# gloria.net
KiCad netlist of a schematic drawn in EAGLE
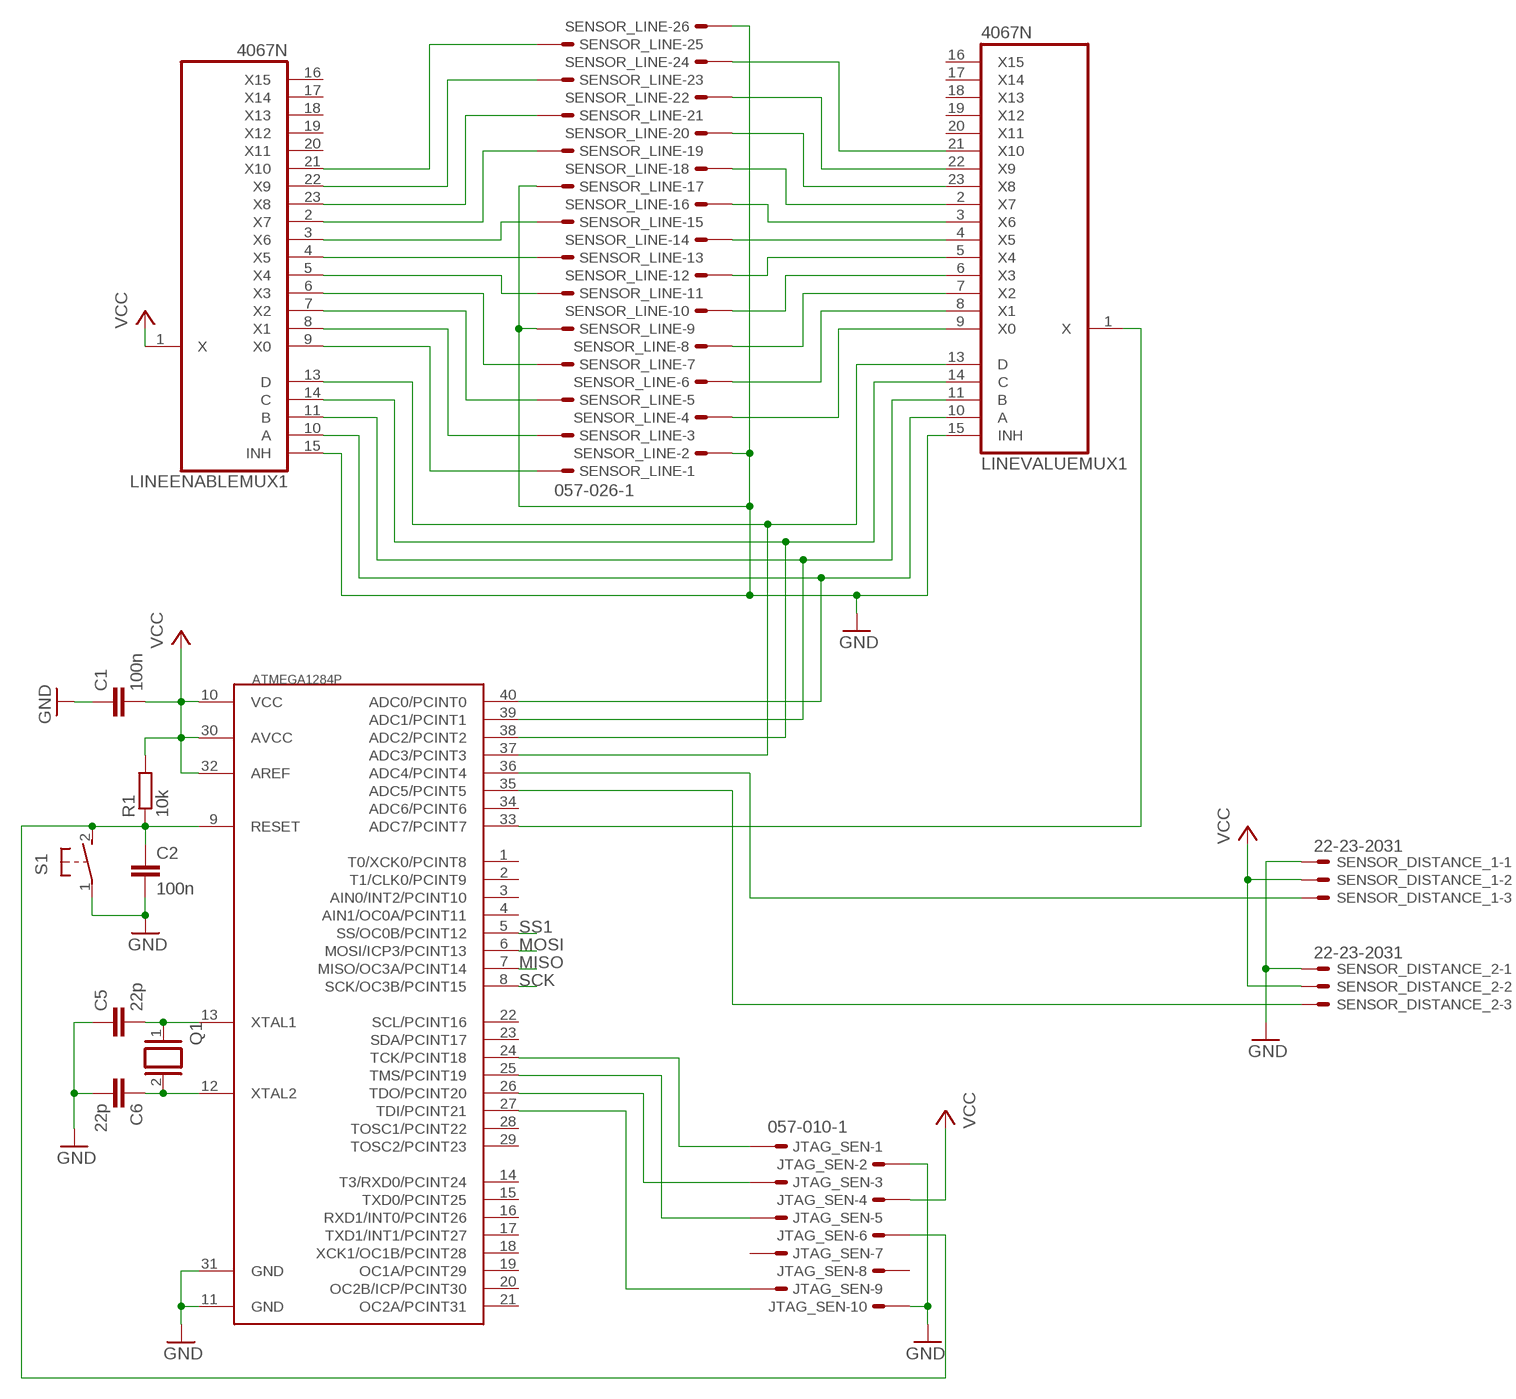
[diagram p0: schematic, sheet 1]
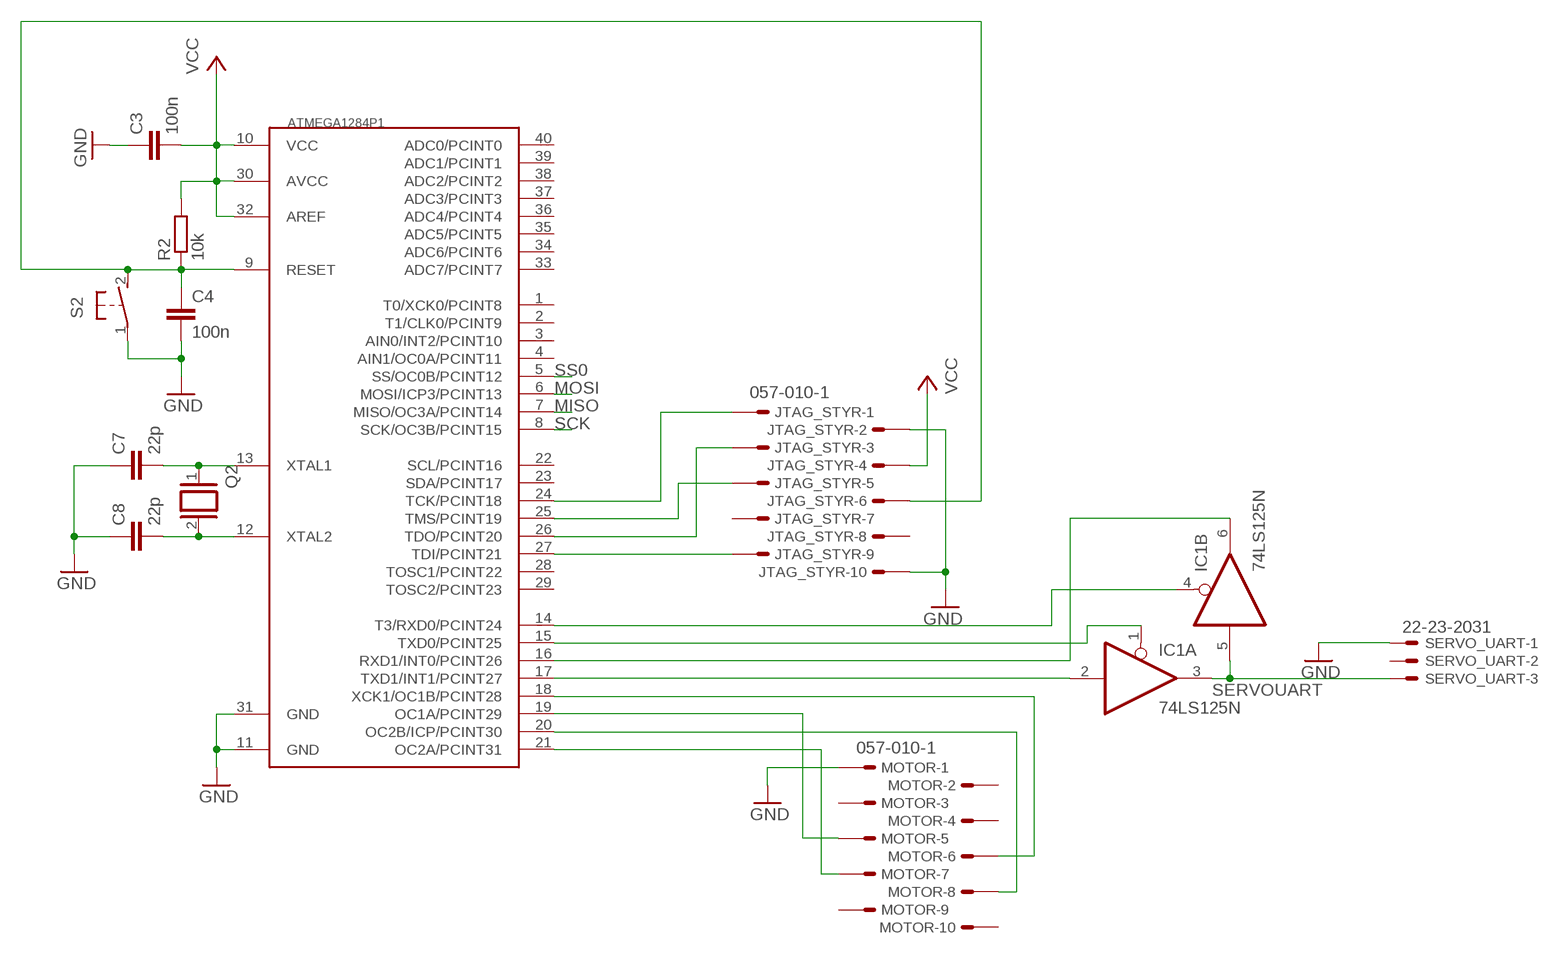
[diagram p1: schematic, sheet 2]
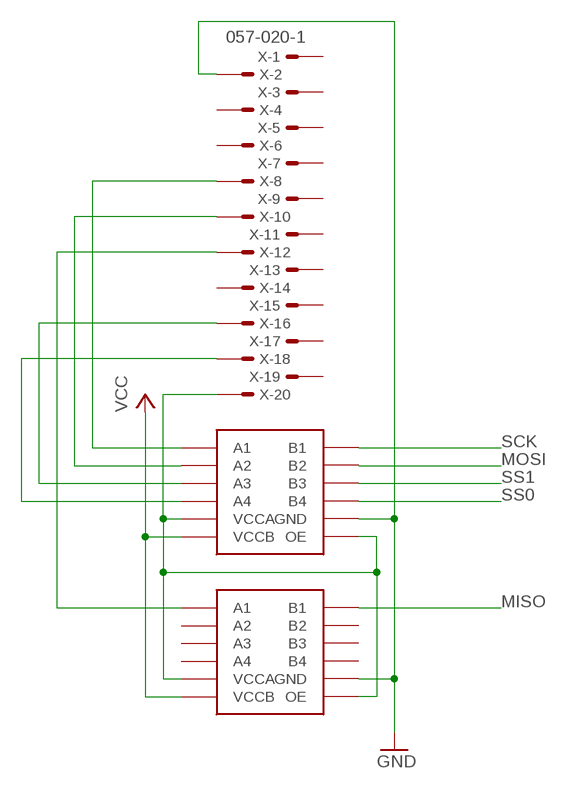
[diagram p2: schematic, sheet 3]

(export (version "E")
  (design (tool "Eeschema 10.0.6"))
  (components
    (comp (ref "ATMEGA1284P1")
      (value "MEGA1284P")
      (footprint "eagle-import:DIL40")
      (libsource (lib "eagle-import") (part "MEGA1284P"))
    )
    (comp (ref "C3")
      (value "100n")
      (footprint "eagle-import:C025-050X050")
      (libsource (lib "eagle-import") (part "C-EU025-050X050"))
    )
    (comp (ref "C4")
      (value "100n")
      (footprint "eagle-import:C025-050X050")
      (libsource (lib "eagle-import") (part "C-EU025-050X050"))
    )
    (comp (ref "C7")
      (value "22p")
      (footprint "eagle-import:C025-050X050")
      (libsource (lib "eagle-import") (part "C-EU025-050X050"))
    )
    (comp (ref "C8")
      (value "22p")
      (footprint "eagle-import:C025-050X050")
      (libsource (lib "eagle-import") (part "C-EU025-050X050"))
    )
    (comp (ref "IC1")
      (value "74LS125N")
      (footprint "eagle-import:DIL14")
      (libsource (lib "eagle-import") (part "74125NLS"))
    )
    (comp (ref "JTAG_STYR")
      (value "057-010-1")
      (footprint "eagle-import:057-010-1")
      (libsource (lib "eagle-import") (part "057-010-1"))
    )
    (comp (ref "MOTOR")
      (value "057-010-1")
      (footprint "eagle-import:057-010-1")
      (libsource (lib "eagle-import") (part "057-010-1"))
    )
    (comp (ref "Q2")
      (value "XTAL/S")
      (footprint "eagle-import:QS")
      (libsource (lib "eagle-import") (part "XTAL/S"))
    )
    (comp (ref "R2")
      (value "10k")
      (footprint "eagle-import:0204V")
      (libsource (lib "eagle-import") (part "R-EU_0204/2V"))
    )
    (comp (ref "S2")
      (value "31-XX")
      (footprint "eagle-import:B3F-31XX")
      (fields (field (name "MPN") "B3F-3100"))
      (libsource (lib "eagle-import") (part "31-XX"))
    )
    (comp (ref "SERVO_UART")
      (value "22-23-2031")
      (footprint "eagle-import:22-23-2031")
      (fields (field (name "MF") "MOLEX"))
      (libsource (lib "eagle-import") (part "22-23-2031"))
    )
    (comp (ref "U$1")
      (value "TXB0104SOIC(D)")
      (footprint "eagle-import:TXB0104")
      (libsource (lib "eagle-import") (part "TXB0104SOIC(D)"))
    )
    (comp (ref "U$2")
      (value "TXB0104SOIC(D)")
      (footprint "eagle-import:TXB0104")
      (libsource (lib "eagle-import") (part "TXB0104SOIC(D)"))
    )
    (comp (ref "X")
      (value "057-020-1")
      (footprint "eagle-import:057-020-1")
      (libsource (lib "eagle-import") (part "057-020-1"))
    )
    (comp (ref "ATMEGA1284P")
      (value "MEGA1284P")
      (footprint "eagle-import:DIL40")
      (libsource (lib "eagle-import") (part "MEGA1284P"))
    )
    (comp (ref "C1")
      (value "100n")
      (footprint "eagle-import:C1206")
      (libsource (lib "eagle-import") (part "C-EUC1206"))
    )
    (comp (ref "C2")
      (value "100n")
      (footprint "eagle-import:C1206")
      (libsource (lib "eagle-import") (part "C-EUC1206"))
    )
    (comp (ref "C5")
      (value "22p")
      (footprint "eagle-import:C1206")
      (libsource (lib "eagle-import") (part "C-EUC1206"))
    )
    (comp (ref "C6")
      (value "22p")
      (footprint "eagle-import:C1206")
      (libsource (lib "eagle-import") (part "C-EUC1206"))
    )
    (comp (ref "JTAG_SEN")
      (value "057-010-1")
      (footprint "eagle-import:057-010-1")
      (libsource (lib "eagle-import") (part "057-010-1"))
    )
    (comp (ref "LINEENABLEMUX1")
      (value "4067N")
      (footprint "eagle-import:DIL24-6")
      (libsource (lib "eagle-import") (part "4067N"))
    )
    (comp (ref "LINEVALUEMUX1")
      (value "4067N")
      (footprint "eagle-import:DIL24-6")
      (libsource (lib "eagle-import") (part "4067N"))
    )
    (comp (ref "Q1")
      (value "XTAL/S")
      (footprint "eagle-import:QS")
      (libsource (lib "eagle-import") (part "XTAL/S"))
    )
    (comp (ref "R1")
      (value "10k")
      (footprint "eagle-import:V235_17")
      (libsource (lib "eagle-import") (part "R-EU_V235/17"))
    )
    (comp (ref "S1")
      (value "31-XX")
      (footprint "eagle-import:B3F-31XX")
      (fields (field (name "MPN") "B3F-3100"))
      (libsource (lib "eagle-import") (part "31-XX"))
    )
    (comp (ref "SENSOR_DISTANCE_1")
      (value "22-23-2031")
      (footprint "eagle-import:22-23-2031")
      (fields (field (name "MF") "MOLEX"))
      (libsource (lib "eagle-import") (part "22-23-2031"))
    )
    (comp (ref "SENSOR_DISTANCE_2")
      (value "22-23-2031")
      (footprint "eagle-import:22-23-2031")
      (fields (field (name "MF") "MOLEX"))
      (libsource (lib "eagle-import") (part "22-23-2031"))
    )
    (comp (ref "SENSOR_LINE")
      (value "057-026-1")
      (footprint "eagle-import:057-026-1")
      (libsource (lib "eagle-import") (part "057-026-1"))
    )
  )
  (nets
    (net (code "1") (name "GND") (class "Default")
      (node (ref "ATMEGA1284P") (pin "11") (pinfunction "GND_11") (pintype "bidirectional"))
      (node (ref "ATMEGA1284P") (pin "31") (pinfunction "GND_31") (pintype "bidirectional"))
      (node (ref "ATMEGA1284P1") (pin "11") (pinfunction "GND_11") (pintype "bidirectional"))
      (node (ref "ATMEGA1284P1") (pin "31") (pinfunction "GND_31") (pintype "bidirectional"))
      (node (ref "C1") (pin "1") (pinfunction "1_1") (pintype "passive"))
      (node (ref "C2") (pin "2") (pinfunction "2_2") (pintype "passive"))
      (node (ref "C3") (pin "1") (pinfunction "1_1") (pintype "passive"))
      (node (ref "C4") (pin "2") (pinfunction "2_2") (pintype "passive"))
      (node (ref "C5") (pin "1") (pinfunction "1_1") (pintype "passive"))
      (node (ref "C6") (pin "2") (pinfunction "2_2") (pintype "passive"))
      (node (ref "C7") (pin "1") (pinfunction "1_1") (pintype "passive"))
      (node (ref "C8") (pin "1") (pinfunction "1_1") (pintype "passive"))
      (node (ref "JTAG_SEN") (pin "10") (pinfunction "S_10") (pintype "passive"))
      (node (ref "JTAG_SEN") (pin "2") (pinfunction "S_2") (pintype "passive"))
      (node (ref "JTAG_STYR") (pin "10") (pinfunction "S_10") (pintype "passive"))
      (node (ref "JTAG_STYR") (pin "2") (pinfunction "S_2") (pintype "passive"))
      (node (ref "LINEENABLEMUX1") (pin "15") (pinfunction "INH_15") (pintype "input"))
      (node (ref "LINEVALUEMUX1") (pin "15") (pinfunction "INH_15") (pintype "input"))
      (node (ref "MOTOR") (pin "1") (pinfunction "S_1") (pintype "passive"))
      (node (ref "S1") (pin "1") (pinfunction "P_1") (pintype "passive"))
      (node (ref "S2") (pin "1") (pinfunction "P_1") (pintype "passive"))
      (node (ref "SENSOR_DISTANCE_1") (pin "1") (pinfunction "S_1") (pintype "passive"))
      (node (ref "SENSOR_DISTANCE_2") (pin "1") (pinfunction "S_1") (pintype "passive"))
      (node (ref "SENSOR_LINE") (pin "17") (pinfunction "S_17") (pintype "passive"))
      (node (ref "SENSOR_LINE") (pin "2") (pinfunction "S_2") (pintype "passive"))
      (node (ref "SENSOR_LINE") (pin "26") (pinfunction "S_26") (pintype "passive"))
      (node (ref "SENSOR_LINE") (pin "9") (pinfunction "S_9") (pintype "passive"))
      (node (ref "SERVO_UART") (pin "1") (pinfunction "S_1") (pintype "passive"))
      (node (ref "U$1") (pin "P$7") (pinfunction "GND_P$7") (pintype "bidirectional"))
      (node (ref "U$2") (pin "P$7") (pinfunction "GND_P$7") (pintype "bidirectional"))
      (node (ref "X") (pin "2") (pinfunction "S_2") (pintype "passive"))
    )
    (net (code "2") (name "MISO") (class "Default")
      (node (ref "ATMEGA1284P") (pin "7") (pinfunction "MISO/OC3A/PCINT14_7") (pintype "bidirectional"))
      (node (ref "ATMEGA1284P1") (pin "7") (pinfunction "MISO/OC3A/PCINT14_7") (pintype "bidirectional"))
      (node (ref "U$2") (pin "P$13") (pinfunction "B1_P$13") (pintype "bidirectional"))
    )
    (net (code "3") (name "MOSI") (class "Default")
      (node (ref "ATMEGA1284P") (pin "6") (pinfunction "MOSI/ICP3/PCINT13_6") (pintype "bidirectional"))
      (node (ref "ATMEGA1284P1") (pin "6") (pinfunction "MOSI/ICP3/PCINT13_6") (pintype "bidirectional"))
      (node (ref "U$1") (pin "P$12") (pinfunction "B2_P$12") (pintype "bidirectional"))
    )
    (net (code "4") (name "Net-(ATMEGA1284P-ADC0{slash}PCINT0)") (class "Default")
      (node (ref "ATMEGA1284P") (pin "40") (pinfunction "ADC0/PCINT0_40") (pintype "bidirectional"))
      (node (ref "LINEENABLEMUX1") (pin "10") (pinfunction "A_10") (pintype "input"))
      (node (ref "LINEVALUEMUX1") (pin "10") (pinfunction "A_10") (pintype "input"))
    )
    (net (code "5") (name "Net-(ATMEGA1284P-ADC1{slash}PCINT1)") (class "Default")
      (node (ref "ATMEGA1284P") (pin "39") (pinfunction "ADC1/PCINT1_39") (pintype "bidirectional"))
      (node (ref "LINEENABLEMUX1") (pin "11") (pinfunction "B_11") (pintype "input"))
      (node (ref "LINEVALUEMUX1") (pin "11") (pinfunction "B_11") (pintype "input"))
    )
    (net (code "6") (name "Net-(ATMEGA1284P-ADC2{slash}PCINT2)") (class "Default")
      (node (ref "ATMEGA1284P") (pin "38") (pinfunction "ADC2/PCINT2_38") (pintype "bidirectional"))
      (node (ref "LINEENABLEMUX1") (pin "14") (pinfunction "C_14") (pintype "input"))
      (node (ref "LINEVALUEMUX1") (pin "14") (pinfunction "C_14") (pintype "input"))
    )
    (net (code "7") (name "Net-(ATMEGA1284P-ADC3{slash}PCINT3)") (class "Default")
      (node (ref "ATMEGA1284P") (pin "37") (pinfunction "ADC3/PCINT3_37") (pintype "bidirectional"))
      (node (ref "LINEENABLEMUX1") (pin "13") (pinfunction "D_13") (pintype "input"))
      (node (ref "LINEVALUEMUX1") (pin "13") (pinfunction "D_13") (pintype "input"))
    )
    (net (code "8") (name "Net-(ATMEGA1284P-ADC4{slash}PCINT4)") (class "Default")
      (node (ref "ATMEGA1284P") (pin "36") (pinfunction "ADC4/PCINT4_36") (pintype "bidirectional"))
      (node (ref "SENSOR_DISTANCE_1") (pin "3") (pinfunction "S_3") (pintype "passive"))
    )
    (net (code "9") (name "Net-(ATMEGA1284P-ADC5{slash}PCINT5)") (class "Default")
      (node (ref "ATMEGA1284P") (pin "35") (pinfunction "ADC5/PCINT5_35") (pintype "bidirectional"))
      (node (ref "SENSOR_DISTANCE_2") (pin "3") (pinfunction "S_3") (pintype "passive"))
    )
    (net (code "10") (name "Net-(ATMEGA1284P-ADC7{slash}PCINT7)") (class "Default")
      (node (ref "ATMEGA1284P") (pin "33") (pinfunction "ADC7/PCINT7_33") (pintype "bidirectional"))
      (node (ref "LINEVALUEMUX1") (pin "1") (pinfunction "X_1") (pintype "output"))
    )
    (net (code "11") (name "Net-(ATMEGA1284P-RESET)") (class "Default")
      (node (ref "ATMEGA1284P") (pin "9") (pinfunction "RESET_9") (pintype "bidirectional"))
      (node (ref "C2") (pin "1") (pinfunction "1_1") (pintype "passive"))
      (node (ref "JTAG_SEN") (pin "6") (pinfunction "S_6") (pintype "passive"))
      (node (ref "R1") (pin "1") (pinfunction "1_1") (pintype "passive"))
      (node (ref "S1") (pin "2") (pinfunction "S_2") (pintype "passive"))
    )
    (net (code "12") (name "Net-(ATMEGA1284P-TCK{slash}PCINT18)") (class "Default")
      (node (ref "ATMEGA1284P") (pin "24") (pinfunction "TCK/PCINT18_24") (pintype "bidirectional"))
      (node (ref "JTAG_SEN") (pin "1") (pinfunction "S_1") (pintype "passive"))
    )
    (net (code "13") (name "Net-(ATMEGA1284P-TDI{slash}PCINT21)") (class "Default")
      (node (ref "ATMEGA1284P") (pin "27") (pinfunction "TDI/PCINT21_27") (pintype "bidirectional"))
      (node (ref "JTAG_SEN") (pin "9") (pinfunction "S_9") (pintype "passive"))
    )
    (net (code "14") (name "Net-(ATMEGA1284P-TDO{slash}PCINT20)") (class "Default")
      (node (ref "ATMEGA1284P") (pin "26") (pinfunction "TDO/PCINT20_26") (pintype "bidirectional"))
      (node (ref "JTAG_SEN") (pin "3") (pinfunction "S_3") (pintype "passive"))
    )
    (net (code "15") (name "Net-(ATMEGA1284P-TMS{slash}PCINT19)") (class "Default")
      (node (ref "ATMEGA1284P") (pin "25") (pinfunction "TMS/PCINT19_25") (pintype "bidirectional"))
      (node (ref "JTAG_SEN") (pin "5") (pinfunction "S_5") (pintype "passive"))
    )
    (net (code "16") (name "Net-(ATMEGA1284P-XTAL1)") (class "Default")
      (node (ref "ATMEGA1284P") (pin "13") (pinfunction "XTAL1_13") (pintype "bidirectional"))
      (node (ref "C5") (pin "2") (pinfunction "2_2") (pintype "passive"))
      (node (ref "Q1") (pin "1") (pinfunction "1_1") (pintype "passive"))
    )
    (net (code "17") (name "Net-(ATMEGA1284P-XTAL2)") (class "Default")
      (node (ref "ATMEGA1284P") (pin "12") (pinfunction "XTAL2_12") (pintype "bidirectional"))
      (node (ref "C6") (pin "1") (pinfunction "1_1") (pintype "passive"))
      (node (ref "Q1") (pin "2") (pinfunction "2_2") (pintype "passive"))
    )
    (net (code "18") (name "Net-(ATMEGA1284P1-OC1A{slash}PCINT29)") (class "Default")
      (node (ref "ATMEGA1284P1") (pin "19") (pinfunction "OC1A/PCINT29_19") (pintype "bidirectional"))
      (node (ref "MOTOR") (pin "5") (pinfunction "S_5") (pintype "passive"))
    )
    (net (code "19") (name "Net-(ATMEGA1284P1-OC2A{slash}PCINT31)") (class "Default")
      (node (ref "ATMEGA1284P1") (pin "21") (pinfunction "OC2A/PCINT31_21") (pintype "bidirectional"))
      (node (ref "MOTOR") (pin "7") (pinfunction "S_7") (pintype "passive"))
    )
    (net (code "20") (name "Net-(ATMEGA1284P1-OC2B{slash}ICP{slash}PCINT30)") (class "Default")
      (node (ref "ATMEGA1284P1") (pin "20") (pinfunction "OC2B/ICP/PCINT30_20") (pintype "bidirectional"))
      (node (ref "MOTOR") (pin "8") (pinfunction "S_8") (pintype "passive"))
    )
    (net (code "21") (name "Net-(ATMEGA1284P1-RESET)") (class "Default")
      (node (ref "ATMEGA1284P1") (pin "9") (pinfunction "RESET_9") (pintype "bidirectional"))
      (node (ref "C4") (pin "1") (pinfunction "1_1") (pintype "passive"))
      (node (ref "JTAG_STYR") (pin "6") (pinfunction "S_6") (pintype "passive"))
      (node (ref "R2") (pin "1") (pinfunction "1_1") (pintype "passive"))
      (node (ref "S2") (pin "2") (pinfunction "S_2") (pintype "passive"))
    )
    (net (code "22") (name "Net-(ATMEGA1284P1-RXD1{slash}INT0{slash}PCINT26)") (class "Default")
      (node (ref "ATMEGA1284P1") (pin "16") (pinfunction "RXD1/INT0/PCINT26_16") (pintype "bidirectional"))
      (node (ref "IC1") (pin "6") (pinfunction "O_6") (pintype "tri_state"))
    )
    (net (code "23") (name "Net-(ATMEGA1284P1-T3{slash}RXD0{slash}PCINT24)") (class "Default")
      (node (ref "ATMEGA1284P1") (pin "14") (pinfunction "T3/RXD0/PCINT24_14") (pintype "bidirectional"))
      (node (ref "IC1") (pin "4") (pinfunction "OE_4") (pintype "input"))
    )
    (net (code "24") (name "Net-(ATMEGA1284P1-TCK{slash}PCINT18)") (class "Default")
      (node (ref "ATMEGA1284P1") (pin "24") (pinfunction "TCK/PCINT18_24") (pintype "bidirectional"))
      (node (ref "JTAG_STYR") (pin "1") (pinfunction "S_1") (pintype "passive"))
    )
    (net (code "25") (name "Net-(ATMEGA1284P1-TDI{slash}PCINT21)") (class "Default")
      (node (ref "ATMEGA1284P1") (pin "27") (pinfunction "TDI/PCINT21_27") (pintype "bidirectional"))
      (node (ref "JTAG_STYR") (pin "9") (pinfunction "S_9") (pintype "passive"))
    )
    (net (code "26") (name "Net-(ATMEGA1284P1-TDO{slash}PCINT20)") (class "Default")
      (node (ref "ATMEGA1284P1") (pin "26") (pinfunction "TDO/PCINT20_26") (pintype "bidirectional"))
      (node (ref "JTAG_STYR") (pin "3") (pinfunction "S_3") (pintype "passive"))
    )
    (net (code "27") (name "Net-(ATMEGA1284P1-TMS{slash}PCINT19)") (class "Default")
      (node (ref "ATMEGA1284P1") (pin "25") (pinfunction "TMS/PCINT19_25") (pintype "bidirectional"))
      (node (ref "JTAG_STYR") (pin "5") (pinfunction "S_5") (pintype "passive"))
    )
    (net (code "28") (name "Net-(ATMEGA1284P1-TXD0{slash}PCINT25)") (class "Default")
      (node (ref "ATMEGA1284P1") (pin "15") (pinfunction "TXD0/PCINT25_15") (pintype "bidirectional"))
      (node (ref "IC1") (pin "1") (pinfunction "OE_1") (pintype "input"))
    )
    (net (code "29") (name "Net-(ATMEGA1284P1-TXD1{slash}INT1{slash}PCINT27)") (class "Default")
      (node (ref "ATMEGA1284P1") (pin "17") (pinfunction "TXD1/INT1/PCINT27_17") (pintype "bidirectional"))
      (node (ref "IC1") (pin "2") (pinfunction "I_2") (pintype "input"))
    )
    (net (code "30") (name "Net-(ATMEGA1284P1-XCK1{slash}OC1B{slash}PCINT28)") (class "Default")
      (node (ref "ATMEGA1284P1") (pin "18") (pinfunction "XCK1/OC1B/PCINT28_18") (pintype "bidirectional"))
      (node (ref "MOTOR") (pin "6") (pinfunction "S_6") (pintype "passive"))
    )
    (net (code "31") (name "Net-(ATMEGA1284P1-XTAL1)") (class "Default")
      (node (ref "ATMEGA1284P1") (pin "13") (pinfunction "XTAL1_13") (pintype "bidirectional"))
      (node (ref "C7") (pin "2") (pinfunction "2_2") (pintype "passive"))
      (node (ref "Q2") (pin "1") (pinfunction "1_1") (pintype "passive"))
    )
    (net (code "32") (name "Net-(ATMEGA1284P1-XTAL2)") (class "Default")
      (node (ref "ATMEGA1284P1") (pin "12") (pinfunction "XTAL2_12") (pintype "bidirectional"))
      (node (ref "C8") (pin "2") (pinfunction "2_2") (pintype "passive"))
      (node (ref "Q2") (pin "2") (pinfunction "2_2") (pintype "passive"))
    )
    (net (code "33") (name "Net-(LINEENABLEMUX1A-X0)") (class "Default")
      (node (ref "LINEENABLEMUX1") (pin "9") (pinfunction "X0_9") (pintype "input"))
      (node (ref "SENSOR_LINE") (pin "1") (pinfunction "S_1") (pintype "passive"))
    )
    (net (code "34") (name "Net-(LINEENABLEMUX1A-X1)") (class "Default")
      (node (ref "LINEENABLEMUX1") (pin "8") (pinfunction "X1_8") (pintype "input"))
      (node (ref "SENSOR_LINE") (pin "3") (pinfunction "S_3") (pintype "passive"))
    )
    (net (code "35") (name "Net-(LINEENABLEMUX1A-X2)") (class "Default")
      (node (ref "LINEENABLEMUX1") (pin "7") (pinfunction "X2_7") (pintype "input"))
      (node (ref "SENSOR_LINE") (pin "5") (pinfunction "S_5") (pintype "passive"))
    )
    (net (code "36") (name "Net-(LINEENABLEMUX1A-X3)") (class "Default")
      (node (ref "LINEENABLEMUX1") (pin "6") (pinfunction "X3_6") (pintype "input"))
      (node (ref "SENSOR_LINE") (pin "7") (pinfunction "S_7") (pintype "passive"))
    )
    (net (code "37") (name "Net-(LINEENABLEMUX1A-X4)") (class "Default")
      (node (ref "LINEENABLEMUX1") (pin "5") (pinfunction "X4_5") (pintype "input"))
      (node (ref "SENSOR_LINE") (pin "11") (pinfunction "S_11") (pintype "passive"))
    )
    (net (code "38") (name "Net-(LINEENABLEMUX1A-X5)") (class "Default")
      (node (ref "LINEENABLEMUX1") (pin "4") (pinfunction "X5_4") (pintype "input"))
      (node (ref "SENSOR_LINE") (pin "13") (pinfunction "S_13") (pintype "passive"))
    )
    (net (code "39") (name "Net-(LINEENABLEMUX1A-X6)") (class "Default")
      (node (ref "LINEENABLEMUX1") (pin "3") (pinfunction "X6_3") (pintype "input"))
      (node (ref "SENSOR_LINE") (pin "15") (pinfunction "S_15") (pintype "passive"))
    )
    (net (code "40") (name "Net-(LINEENABLEMUX1A-X7)") (class "Default")
      (node (ref "LINEENABLEMUX1") (pin "2") (pinfunction "X7_2") (pintype "input"))
      (node (ref "SENSOR_LINE") (pin "19") (pinfunction "S_19") (pintype "passive"))
    )
    (net (code "41") (name "Net-(LINEENABLEMUX1A-X8)") (class "Default")
      (node (ref "LINEENABLEMUX1") (pin "23") (pinfunction "X8_23") (pintype "input"))
      (node (ref "SENSOR_LINE") (pin "21") (pinfunction "S_21") (pintype "passive"))
    )
    (net (code "42") (name "Net-(LINEENABLEMUX1A-X9)") (class "Default")
      (node (ref "LINEENABLEMUX1") (pin "22") (pinfunction "X9_22") (pintype "input"))
      (node (ref "SENSOR_LINE") (pin "23") (pinfunction "S_23") (pintype "passive"))
    )
    (net (code "43") (name "Net-(LINEENABLEMUX1A-X10)") (class "Default")
      (node (ref "LINEENABLEMUX1") (pin "21") (pinfunction "X10_21") (pintype "input"))
      (node (ref "SENSOR_LINE") (pin "25") (pinfunction "S_25") (pintype "passive"))
    )
    (net (code "44") (name "Net-(LINEVALUEMUX1A-X0)") (class "Default")
      (node (ref "LINEVALUEMUX1") (pin "9") (pinfunction "X0_9") (pintype "input"))
      (node (ref "SENSOR_LINE") (pin "4") (pinfunction "S_4") (pintype "passive"))
    )
    (net (code "45") (name "Net-(LINEVALUEMUX1A-X1)") (class "Default")
      (node (ref "LINEVALUEMUX1") (pin "8") (pinfunction "X1_8") (pintype "input"))
      (node (ref "SENSOR_LINE") (pin "6") (pinfunction "S_6") (pintype "passive"))
    )
    (net (code "46") (name "Net-(LINEVALUEMUX1A-X2)") (class "Default")
      (node (ref "LINEVALUEMUX1") (pin "7") (pinfunction "X2_7") (pintype "input"))
      (node (ref "SENSOR_LINE") (pin "8") (pinfunction "S_8") (pintype "passive"))
    )
    (net (code "47") (name "Net-(LINEVALUEMUX1A-X3)") (class "Default")
      (node (ref "LINEVALUEMUX1") (pin "6") (pinfunction "X3_6") (pintype "input"))
      (node (ref "SENSOR_LINE") (pin "10") (pinfunction "S_10") (pintype "passive"))
    )
    (net (code "48") (name "Net-(LINEVALUEMUX1A-X4)") (class "Default")
      (node (ref "LINEVALUEMUX1") (pin "5") (pinfunction "X4_5") (pintype "input"))
      (node (ref "SENSOR_LINE") (pin "12") (pinfunction "S_12") (pintype "passive"))
    )
    (net (code "49") (name "Net-(LINEVALUEMUX1A-X5)") (class "Default")
      (node (ref "LINEVALUEMUX1") (pin "4") (pinfunction "X5_4") (pintype "input"))
      (node (ref "SENSOR_LINE") (pin "14") (pinfunction "S_14") (pintype "passive"))
    )
    (net (code "50") (name "Net-(LINEVALUEMUX1A-X6)") (class "Default")
      (node (ref "LINEVALUEMUX1") (pin "3") (pinfunction "X6_3") (pintype "input"))
      (node (ref "SENSOR_LINE") (pin "16") (pinfunction "S_16") (pintype "passive"))
    )
    (net (code "51") (name "Net-(LINEVALUEMUX1A-X7)") (class "Default")
      (node (ref "LINEVALUEMUX1") (pin "2") (pinfunction "X7_2") (pintype "input"))
      (node (ref "SENSOR_LINE") (pin "18") (pinfunction "S_18") (pintype "passive"))
    )
    (net (code "52") (name "Net-(LINEVALUEMUX1A-X8)") (class "Default")
      (node (ref "LINEVALUEMUX1") (pin "23") (pinfunction "X8_23") (pintype "input"))
      (node (ref "SENSOR_LINE") (pin "20") (pinfunction "S_20") (pintype "passive"))
    )
    (net (code "53") (name "Net-(LINEVALUEMUX1A-X9)") (class "Default")
      (node (ref "LINEVALUEMUX1") (pin "22") (pinfunction "X9_22") (pintype "input"))
      (node (ref "SENSOR_LINE") (pin "22") (pinfunction "S_22") (pintype "passive"))
    )
    (net (code "54") (name "Net-(LINEVALUEMUX1A-X10)") (class "Default")
      (node (ref "LINEVALUEMUX1") (pin "21") (pinfunction "X10_21") (pintype "input"))
      (node (ref "SENSOR_LINE") (pin "24") (pinfunction "S_24") (pintype "passive"))
    )
    (net (code "55") (name "Net-(U$1-A1)") (class "Default")
      (node (ref "U$1") (pin "P$2") (pinfunction "A1_P$2") (pintype "bidirectional"))
      (node (ref "X") (pin "8") (pinfunction "S_8") (pintype "passive"))
    )
    (net (code "56") (name "Net-(U$1-A2)") (class "Default")
      (node (ref "U$1") (pin "P$3") (pinfunction "A2_P$3") (pintype "bidirectional"))
      (node (ref "X") (pin "10") (pinfunction "S_10") (pintype "passive"))
    )
    (net (code "57") (name "Net-(U$1-A3)") (class "Default")
      (node (ref "U$1") (pin "P$4") (pinfunction "A3_P$4") (pintype "bidirectional"))
      (node (ref "X") (pin "16") (pinfunction "S_16") (pintype "passive"))
    )
    (net (code "58") (name "Net-(U$1-A4)") (class "Default")
      (node (ref "U$1") (pin "P$5") (pinfunction "A4_P$5") (pintype "bidirectional"))
      (node (ref "X") (pin "18") (pinfunction "S_18") (pintype "passive"))
    )
    (net (code "59") (name "Net-(U$1-OE)") (class "Default")
      (node (ref "U$1") (pin "P$1") (pinfunction "VCCA_P$1") (pintype "bidirectional"))
      (node (ref "U$1") (pin "P$8") (pinfunction "OE_P$8") (pintype "bidirectional"))
      (node (ref "U$2") (pin "P$1") (pinfunction "VCCA_P$1") (pintype "bidirectional"))
      (node (ref "U$2") (pin "P$8") (pinfunction "OE_P$8") (pintype "bidirectional"))
      (node (ref "X") (pin "20") (pinfunction "S_20") (pintype "passive"))
    )
    (net (code "60") (name "Net-(U$2-A1)") (class "Default")
      (node (ref "U$2") (pin "P$2") (pinfunction "A1_P$2") (pintype "bidirectional"))
      (node (ref "X") (pin "12") (pinfunction "S_12") (pintype "passive"))
    )
    (net (code "61") (name "SCK") (class "Default")
      (node (ref "ATMEGA1284P") (pin "8") (pinfunction "SCK/OC3B/PCINT15_8") (pintype "bidirectional"))
      (node (ref "ATMEGA1284P1") (pin "8") (pinfunction "SCK/OC3B/PCINT15_8") (pintype "bidirectional"))
      (node (ref "U$1") (pin "P$13") (pinfunction "B1_P$13") (pintype "bidirectional"))
    )
    (net (code "62") (name "SERVOUART") (class "Default")
      (node (ref "IC1") (pin "3") (pinfunction "O_3") (pintype "tri_state"))
      (node (ref "IC1") (pin "5") (pinfunction "I_5") (pintype "input"))
      (node (ref "SERVO_UART") (pin "3") (pinfunction "S_3") (pintype "passive"))
    )
    (net (code "63") (name "SS0") (class "Default")
      (node (ref "ATMEGA1284P1") (pin "5") (pinfunction "SS/OC0B/PCINT12_5") (pintype "bidirectional"))
      (node (ref "U$1") (pin "P$10") (pinfunction "B4_P$10") (pintype "bidirectional"))
    )
    (net (code "64") (name "SS1") (class "Default")
      (node (ref "ATMEGA1284P") (pin "5") (pinfunction "SS/OC0B/PCINT12_5") (pintype "bidirectional"))
      (node (ref "U$1") (pin "P$11") (pinfunction "B3_P$11") (pintype "bidirectional"))
    )
    (net (code "65") (name "VCC") (class "Default")
      (node (ref "ATMEGA1284P") (pin "10") (pinfunction "VCC_10") (pintype "bidirectional"))
      (node (ref "ATMEGA1284P") (pin "30") (pinfunction "AVCC_30") (pintype "bidirectional"))
      (node (ref "ATMEGA1284P") (pin "32") (pinfunction "AREF_32") (pintype "bidirectional"))
      (node (ref "ATMEGA1284P1") (pin "10") (pinfunction "VCC_10") (pintype "bidirectional"))
      (node (ref "ATMEGA1284P1") (pin "30") (pinfunction "AVCC_30") (pintype "bidirectional"))
      (node (ref "ATMEGA1284P1") (pin "32") (pinfunction "AREF_32") (pintype "bidirectional"))
      (node (ref "C1") (pin "2") (pinfunction "2_2") (pintype "passive"))
      (node (ref "C3") (pin "2") (pinfunction "2_2") (pintype "passive"))
      (node (ref "JTAG_SEN") (pin "4") (pinfunction "S_4") (pintype "passive"))
      (node (ref "JTAG_STYR") (pin "4") (pinfunction "S_4") (pintype "passive"))
      (node (ref "LINEENABLEMUX1") (pin "1") (pinfunction "X_1") (pintype "output"))
      (node (ref "R1") (pin "2") (pinfunction "2_2") (pintype "passive"))
      (node (ref "R2") (pin "2") (pinfunction "2_2") (pintype "passive"))
      (node (ref "SENSOR_DISTANCE_1") (pin "2") (pinfunction "S_2") (pintype "passive"))
      (node (ref "SENSOR_DISTANCE_2") (pin "2") (pinfunction "S_2") (pintype "passive"))
      (node (ref "U$1") (pin "P$14") (pinfunction "VCCB_P$14") (pintype "bidirectional"))
      (node (ref "U$2") (pin "P$14") (pinfunction "VCCB_P$14") (pintype "bidirectional"))
    )
    (net (code "66") (name "unconnected-(ATMEGA1284P-ADC6{slash}PCINT6-Pad34)") (class "Default")
      (node (ref "ATMEGA1284P") (pin "34") (pinfunction "ADC6/PCINT6_34") (pintype "bidirectional"))
    )
    (net (code "67") (name "unconnected-(ATMEGA1284P-AIN0{slash}INT2{slash}PCINT10-Pad3)") (class "Default")
      (node (ref "ATMEGA1284P") (pin "3") (pinfunction "AIN0/INT2/PCINT10_3") (pintype "bidirectional"))
    )
    (net (code "68") (name "unconnected-(ATMEGA1284P-AIN1{slash}OC0A{slash}PCINT11-Pad4)") (class "Default")
      (node (ref "ATMEGA1284P") (pin "4") (pinfunction "AIN1/OC0A/PCINT11_4") (pintype "bidirectional"))
    )
    (net (code "69") (name "unconnected-(ATMEGA1284P-OC1A{slash}PCINT29-Pad19)") (class "Default")
      (node (ref "ATMEGA1284P") (pin "19") (pinfunction "OC1A/PCINT29_19") (pintype "bidirectional"))
    )
    (net (code "70") (name "unconnected-(ATMEGA1284P-OC2A{slash}PCINT31-Pad21)") (class "Default")
      (node (ref "ATMEGA1284P") (pin "21") (pinfunction "OC2A/PCINT31_21") (pintype "bidirectional"))
    )
    (net (code "71") (name "unconnected-(ATMEGA1284P-OC2B{slash}ICP{slash}PCINT30-Pad20)") (class "Default")
      (node (ref "ATMEGA1284P") (pin "20") (pinfunction "OC2B/ICP/PCINT30_20") (pintype "bidirectional"))
    )
    (net (code "72") (name "unconnected-(ATMEGA1284P-RXD1{slash}INT0{slash}PCINT26-Pad16)") (class "Default")
      (node (ref "ATMEGA1284P") (pin "16") (pinfunction "RXD1/INT0/PCINT26_16") (pintype "bidirectional"))
    )
    (net (code "73") (name "unconnected-(ATMEGA1284P-SCL{slash}PCINT16-Pad22)") (class "Default")
      (node (ref "ATMEGA1284P") (pin "22") (pinfunction "SCL/PCINT16_22") (pintype "bidirectional"))
    )
    (net (code "74") (name "unconnected-(ATMEGA1284P-SDA{slash}PCINT17-Pad23)") (class "Default")
      (node (ref "ATMEGA1284P") (pin "23") (pinfunction "SDA/PCINT17_23") (pintype "bidirectional"))
    )
    (net (code "75") (name "unconnected-(ATMEGA1284P-T0{slash}XCK0{slash}PCINT8-Pad1)") (class "Default")
      (node (ref "ATMEGA1284P") (pin "1") (pinfunction "T0/XCK0/PCINT8_1") (pintype "bidirectional"))
    )
    (net (code "76") (name "unconnected-(ATMEGA1284P-T1{slash}CLK0{slash}PCINT9-Pad2)") (class "Default")
      (node (ref "ATMEGA1284P") (pin "2") (pinfunction "T1/CLK0/PCINT9_2") (pintype "bidirectional"))
    )
    (net (code "77") (name "unconnected-(ATMEGA1284P-T3{slash}RXD0{slash}PCINT24-Pad14)") (class "Default")
      (node (ref "ATMEGA1284P") (pin "14") (pinfunction "T3/RXD0/PCINT24_14") (pintype "bidirectional"))
    )
    (net (code "78") (name "unconnected-(ATMEGA1284P-TOSC1{slash}PCINT22-Pad28)") (class "Default")
      (node (ref "ATMEGA1284P") (pin "28") (pinfunction "TOSC1/PCINT22_28") (pintype "bidirectional"))
    )
    (net (code "79") (name "unconnected-(ATMEGA1284P-TOSC2{slash}PCINT23-Pad29)") (class "Default")
      (node (ref "ATMEGA1284P") (pin "29") (pinfunction "TOSC2/PCINT23_29") (pintype "bidirectional"))
    )
    (net (code "80") (name "unconnected-(ATMEGA1284P-TXD0{slash}PCINT25-Pad15)") (class "Default")
      (node (ref "ATMEGA1284P") (pin "15") (pinfunction "TXD0/PCINT25_15") (pintype "bidirectional"))
    )
    (net (code "81") (name "unconnected-(ATMEGA1284P-TXD1{slash}INT1{slash}PCINT27-Pad17)") (class "Default")
      (node (ref "ATMEGA1284P") (pin "17") (pinfunction "TXD1/INT1/PCINT27_17") (pintype "bidirectional"))
    )
    (net (code "82") (name "unconnected-(ATMEGA1284P-XCK1{slash}OC1B{slash}PCINT28-Pad18)") (class "Default")
      (node (ref "ATMEGA1284P") (pin "18") (pinfunction "XCK1/OC1B/PCINT28_18") (pintype "bidirectional"))
    )
    (net (code "83") (name "unconnected-(ATMEGA1284P1-ADC0{slash}PCINT0-Pad40)") (class "Default")
      (node (ref "ATMEGA1284P1") (pin "40") (pinfunction "ADC0/PCINT0_40") (pintype "bidirectional"))
    )
    (net (code "84") (name "unconnected-(ATMEGA1284P1-ADC1{slash}PCINT1-Pad39)") (class "Default")
      (node (ref "ATMEGA1284P1") (pin "39") (pinfunction "ADC1/PCINT1_39") (pintype "bidirectional"))
    )
    (net (code "85") (name "unconnected-(ATMEGA1284P1-ADC2{slash}PCINT2-Pad38)") (class "Default")
      (node (ref "ATMEGA1284P1") (pin "38") (pinfunction "ADC2/PCINT2_38") (pintype "bidirectional"))
    )
    (net (code "86") (name "unconnected-(ATMEGA1284P1-ADC3{slash}PCINT3-Pad37)") (class "Default")
      (node (ref "ATMEGA1284P1") (pin "37") (pinfunction "ADC3/PCINT3_37") (pintype "bidirectional"))
    )
    (net (code "87") (name "unconnected-(ATMEGA1284P1-ADC4{slash}PCINT4-Pad36)") (class "Default")
      (node (ref "ATMEGA1284P1") (pin "36") (pinfunction "ADC4/PCINT4_36") (pintype "bidirectional"))
    )
    (net (code "88") (name "unconnected-(ATMEGA1284P1-ADC5{slash}PCINT5-Pad35)") (class "Default")
      (node (ref "ATMEGA1284P1") (pin "35") (pinfunction "ADC5/PCINT5_35") (pintype "bidirectional"))
    )
    (net (code "89") (name "unconnected-(ATMEGA1284P1-ADC6{slash}PCINT6-Pad34)") (class "Default")
      (node (ref "ATMEGA1284P1") (pin "34") (pinfunction "ADC6/PCINT6_34") (pintype "bidirectional"))
    )
    (net (code "90") (name "unconnected-(ATMEGA1284P1-ADC7{slash}PCINT7-Pad33)") (class "Default")
      (node (ref "ATMEGA1284P1") (pin "33") (pinfunction "ADC7/PCINT7_33") (pintype "bidirectional"))
    )
    (net (code "91") (name "unconnected-(ATMEGA1284P1-AIN0{slash}INT2{slash}PCINT10-Pad3)") (class "Default")
      (node (ref "ATMEGA1284P1") (pin "3") (pinfunction "AIN0/INT2/PCINT10_3") (pintype "bidirectional"))
    )
    (net (code "92") (name "unconnected-(ATMEGA1284P1-AIN1{slash}OC0A{slash}PCINT11-Pad4)") (class "Default")
      (node (ref "ATMEGA1284P1") (pin "4") (pinfunction "AIN1/OC0A/PCINT11_4") (pintype "bidirectional"))
    )
    (net (code "93") (name "unconnected-(ATMEGA1284P1-SCL{slash}PCINT16-Pad22)") (class "Default")
      (node (ref "ATMEGA1284P1") (pin "22") (pinfunction "SCL/PCINT16_22") (pintype "bidirectional"))
    )
    (net (code "94") (name "unconnected-(ATMEGA1284P1-SDA{slash}PCINT17-Pad23)") (class "Default")
      (node (ref "ATMEGA1284P1") (pin "23") (pinfunction "SDA/PCINT17_23") (pintype "bidirectional"))
    )
    (net (code "95") (name "unconnected-(ATMEGA1284P1-T0{slash}XCK0{slash}PCINT8-Pad1)") (class "Default")
      (node (ref "ATMEGA1284P1") (pin "1") (pinfunction "T0/XCK0/PCINT8_1") (pintype "bidirectional"))
    )
    (net (code "96") (name "unconnected-(ATMEGA1284P1-T1{slash}CLK0{slash}PCINT9-Pad2)") (class "Default")
      (node (ref "ATMEGA1284P1") (pin "2") (pinfunction "T1/CLK0/PCINT9_2") (pintype "bidirectional"))
    )
    (net (code "97") (name "unconnected-(ATMEGA1284P1-TOSC1{slash}PCINT22-Pad28)") (class "Default")
      (node (ref "ATMEGA1284P1") (pin "28") (pinfunction "TOSC1/PCINT22_28") (pintype "bidirectional"))
    )
    (net (code "98") (name "unconnected-(ATMEGA1284P1-TOSC2{slash}PCINT23-Pad29)") (class "Default")
      (node (ref "ATMEGA1284P1") (pin "29") (pinfunction "TOSC2/PCINT23_29") (pintype "bidirectional"))
    )
    (net (code "99") (name "unconnected-(JTAG_SENH-S-Pad7)") (class "Default")
      (node (ref "JTAG_SEN") (pin "7") (pinfunction "S_7") (pintype "passive"))
    )
    (net (code "100") (name "unconnected-(JTAG_SENI-S-Pad8)") (class "Default")
      (node (ref "JTAG_SEN") (pin "8") (pinfunction "S_8") (pintype "passive"))
    )
    (net (code "101") (name "unconnected-(JTAG_STYRH-S-Pad7)") (class "Default")
      (node (ref "JTAG_STYR") (pin "7") (pinfunction "S_7") (pintype "passive"))
    )
    (net (code "102") (name "unconnected-(JTAG_STYRI-S-Pad8)") (class "Default")
      (node (ref "JTAG_STYR") (pin "8") (pinfunction "S_8") (pintype "passive"))
    )
    (net (code "103") (name "unconnected-(LINEENABLEMUX1A-X11-Pad20)") (class "Default")
      (node (ref "LINEENABLEMUX1") (pin "20") (pinfunction "X11_20") (pintype "input"))
    )
    (net (code "104") (name "unconnected-(LINEENABLEMUX1A-X12-Pad19)") (class "Default")
      (node (ref "LINEENABLEMUX1") (pin "19") (pinfunction "X12_19") (pintype "input"))
    )
    (net (code "105") (name "unconnected-(LINEENABLEMUX1A-X13-Pad18)") (class "Default")
      (node (ref "LINEENABLEMUX1") (pin "18") (pinfunction "X13_18") (pintype "input"))
    )
    (net (code "106") (name "unconnected-(LINEENABLEMUX1A-X14-Pad17)") (class "Default")
      (node (ref "LINEENABLEMUX1") (pin "17") (pinfunction "X14_17") (pintype "input"))
    )
    (net (code "107") (name "unconnected-(LINEENABLEMUX1A-X15-Pad16)") (class "Default")
      (node (ref "LINEENABLEMUX1") (pin "16") (pinfunction "X15_16") (pintype "input"))
    )
    (net (code "108") (name "unconnected-(LINEVALUEMUX1A-X11-Pad20)") (class "Default")
      (node (ref "LINEVALUEMUX1") (pin "20") (pinfunction "X11_20") (pintype "input"))
    )
    (net (code "109") (name "unconnected-(LINEVALUEMUX1A-X12-Pad19)") (class "Default")
      (node (ref "LINEVALUEMUX1") (pin "19") (pinfunction "X12_19") (pintype "input"))
    )
    (net (code "110") (name "unconnected-(LINEVALUEMUX1A-X13-Pad18)") (class "Default")
      (node (ref "LINEVALUEMUX1") (pin "18") (pinfunction "X13_18") (pintype "input"))
    )
    (net (code "111") (name "unconnected-(LINEVALUEMUX1A-X14-Pad17)") (class "Default")
      (node (ref "LINEVALUEMUX1") (pin "17") (pinfunction "X14_17") (pintype "input"))
    )
    (net (code "112") (name "unconnected-(LINEVALUEMUX1A-X15-Pad16)") (class "Default")
      (node (ref "LINEVALUEMUX1") (pin "16") (pinfunction "X15_16") (pintype "input"))
    )
    (net (code "113") (name "unconnected-(MOTORB-S-Pad10)") (class "Default")
      (node (ref "MOTOR") (pin "10") (pinfunction "S_10") (pintype "passive"))
    )
    (net (code "114") (name "unconnected-(MOTORC-S-Pad2)") (class "Default")
      (node (ref "MOTOR") (pin "2") (pinfunction "S_2") (pintype "passive"))
    )
    (net (code "115") (name "unconnected-(MOTORD-S-Pad3)") (class "Default")
      (node (ref "MOTOR") (pin "3") (pinfunction "S_3") (pintype "passive"))
    )
    (net (code "116") (name "unconnected-(MOTORE-S-Pad4)") (class "Default")
      (node (ref "MOTOR") (pin "4") (pinfunction "S_4") (pintype "passive"))
    )
    (net (code "117") (name "unconnected-(MOTORJ-S-Pad9)") (class "Default")
      (node (ref "MOTOR") (pin "9") (pinfunction "S_9") (pintype "passive"))
    )
    (net (code "118") (name "unconnected-(SERVO_UARTB-S-Pad2)") (class "Default")
      (node (ref "SERVO_UART") (pin "2") (pinfunction "S_2") (pintype "passive"))
    )
    (net (code "119") (name "unconnected-(U$2-A2-PadP$3)") (class "Default")
      (node (ref "U$2") (pin "P$3") (pinfunction "A2_P$3") (pintype "bidirectional"))
    )
    (net (code "120") (name "unconnected-(U$2-A3-PadP$4)") (class "Default")
      (node (ref "U$2") (pin "P$4") (pinfunction "A3_P$4") (pintype "bidirectional"))
    )
    (net (code "121") (name "unconnected-(U$2-A4-PadP$5)") (class "Default")
      (node (ref "U$2") (pin "P$5") (pinfunction "A4_P$5") (pintype "bidirectional"))
    )
    (net (code "122") (name "unconnected-(U$2-B2-PadP$12)") (class "Default")
      (node (ref "U$2") (pin "P$12") (pinfunction "B2_P$12") (pintype "bidirectional"))
    )
    (net (code "123") (name "unconnected-(U$2-B3-PadP$11)") (class "Default")
      (node (ref "U$2") (pin "P$11") (pinfunction "B3_P$11") (pintype "bidirectional"))
    )
    (net (code "124") (name "unconnected-(U$2-B4-PadP$10)") (class "Default")
      (node (ref "U$2") (pin "P$10") (pinfunction "B4_P$10") (pintype "bidirectional"))
    )
    (net (code "125") (name "unconnected-(XA-S-Pad1)") (class "Default")
      (node (ref "X") (pin "1") (pinfunction "S_1") (pintype "passive"))
    )
    (net (code "126") (name "unconnected-(XC-S-Pad11)") (class "Default")
      (node (ref "X") (pin "11") (pinfunction "S_11") (pintype "passive"))
    )
    (net (code "127") (name "unconnected-(XE-S-Pad13)") (class "Default")
      (node (ref "X") (pin "13") (pinfunction "S_13") (pintype "passive"))
    )
    (net (code "128") (name "unconnected-(XF-S-Pad14)") (class "Default")
      (node (ref "X") (pin "14") (pinfunction "S_14") (pintype "passive"))
    )
    (net (code "129") (name "unconnected-(XG-S-Pad15)") (class "Default")
      (node (ref "X") (pin "15") (pinfunction "S_15") (pintype "passive"))
    )
    (net (code "130") (name "unconnected-(XI-S-Pad17)") (class "Default")
      (node (ref "X") (pin "17") (pinfunction "S_17") (pintype "passive"))
    )
    (net (code "131") (name "unconnected-(XK-S-Pad19)") (class "Default")
      (node (ref "X") (pin "19") (pinfunction "S_19") (pintype "passive"))
    )
    (net (code "132") (name "unconnected-(XN-S-Pad3)") (class "Default")
      (node (ref "X") (pin "3") (pinfunction "S_3") (pintype "passive"))
    )
    (net (code "133") (name "unconnected-(XO-S-Pad4)") (class "Default")
      (node (ref "X") (pin "4") (pinfunction "S_4") (pintype "passive"))
    )
    (net (code "134") (name "unconnected-(XP-S-Pad5)") (class "Default")
      (node (ref "X") (pin "5") (pinfunction "S_5") (pintype "passive"))
    )
    (net (code "135") (name "unconnected-(XQ-S-Pad6)") (class "Default")
      (node (ref "X") (pin "6") (pinfunction "S_6") (pintype "passive"))
    )
    (net (code "136") (name "unconnected-(XR-S-Pad7)") (class "Default")
      (node (ref "X") (pin "7") (pinfunction "S_7") (pintype "passive"))
    )
    (net (code "137") (name "unconnected-(XT-S-Pad9)") (class "Default")
      (node (ref "X") (pin "9") (pinfunction "S_9") (pintype "passive"))
    )
  )
)
